# SCH_MATIASALFARO_PROYECTOFINAL.net
KiCad netlist of a schematic drawn in Altium Designer
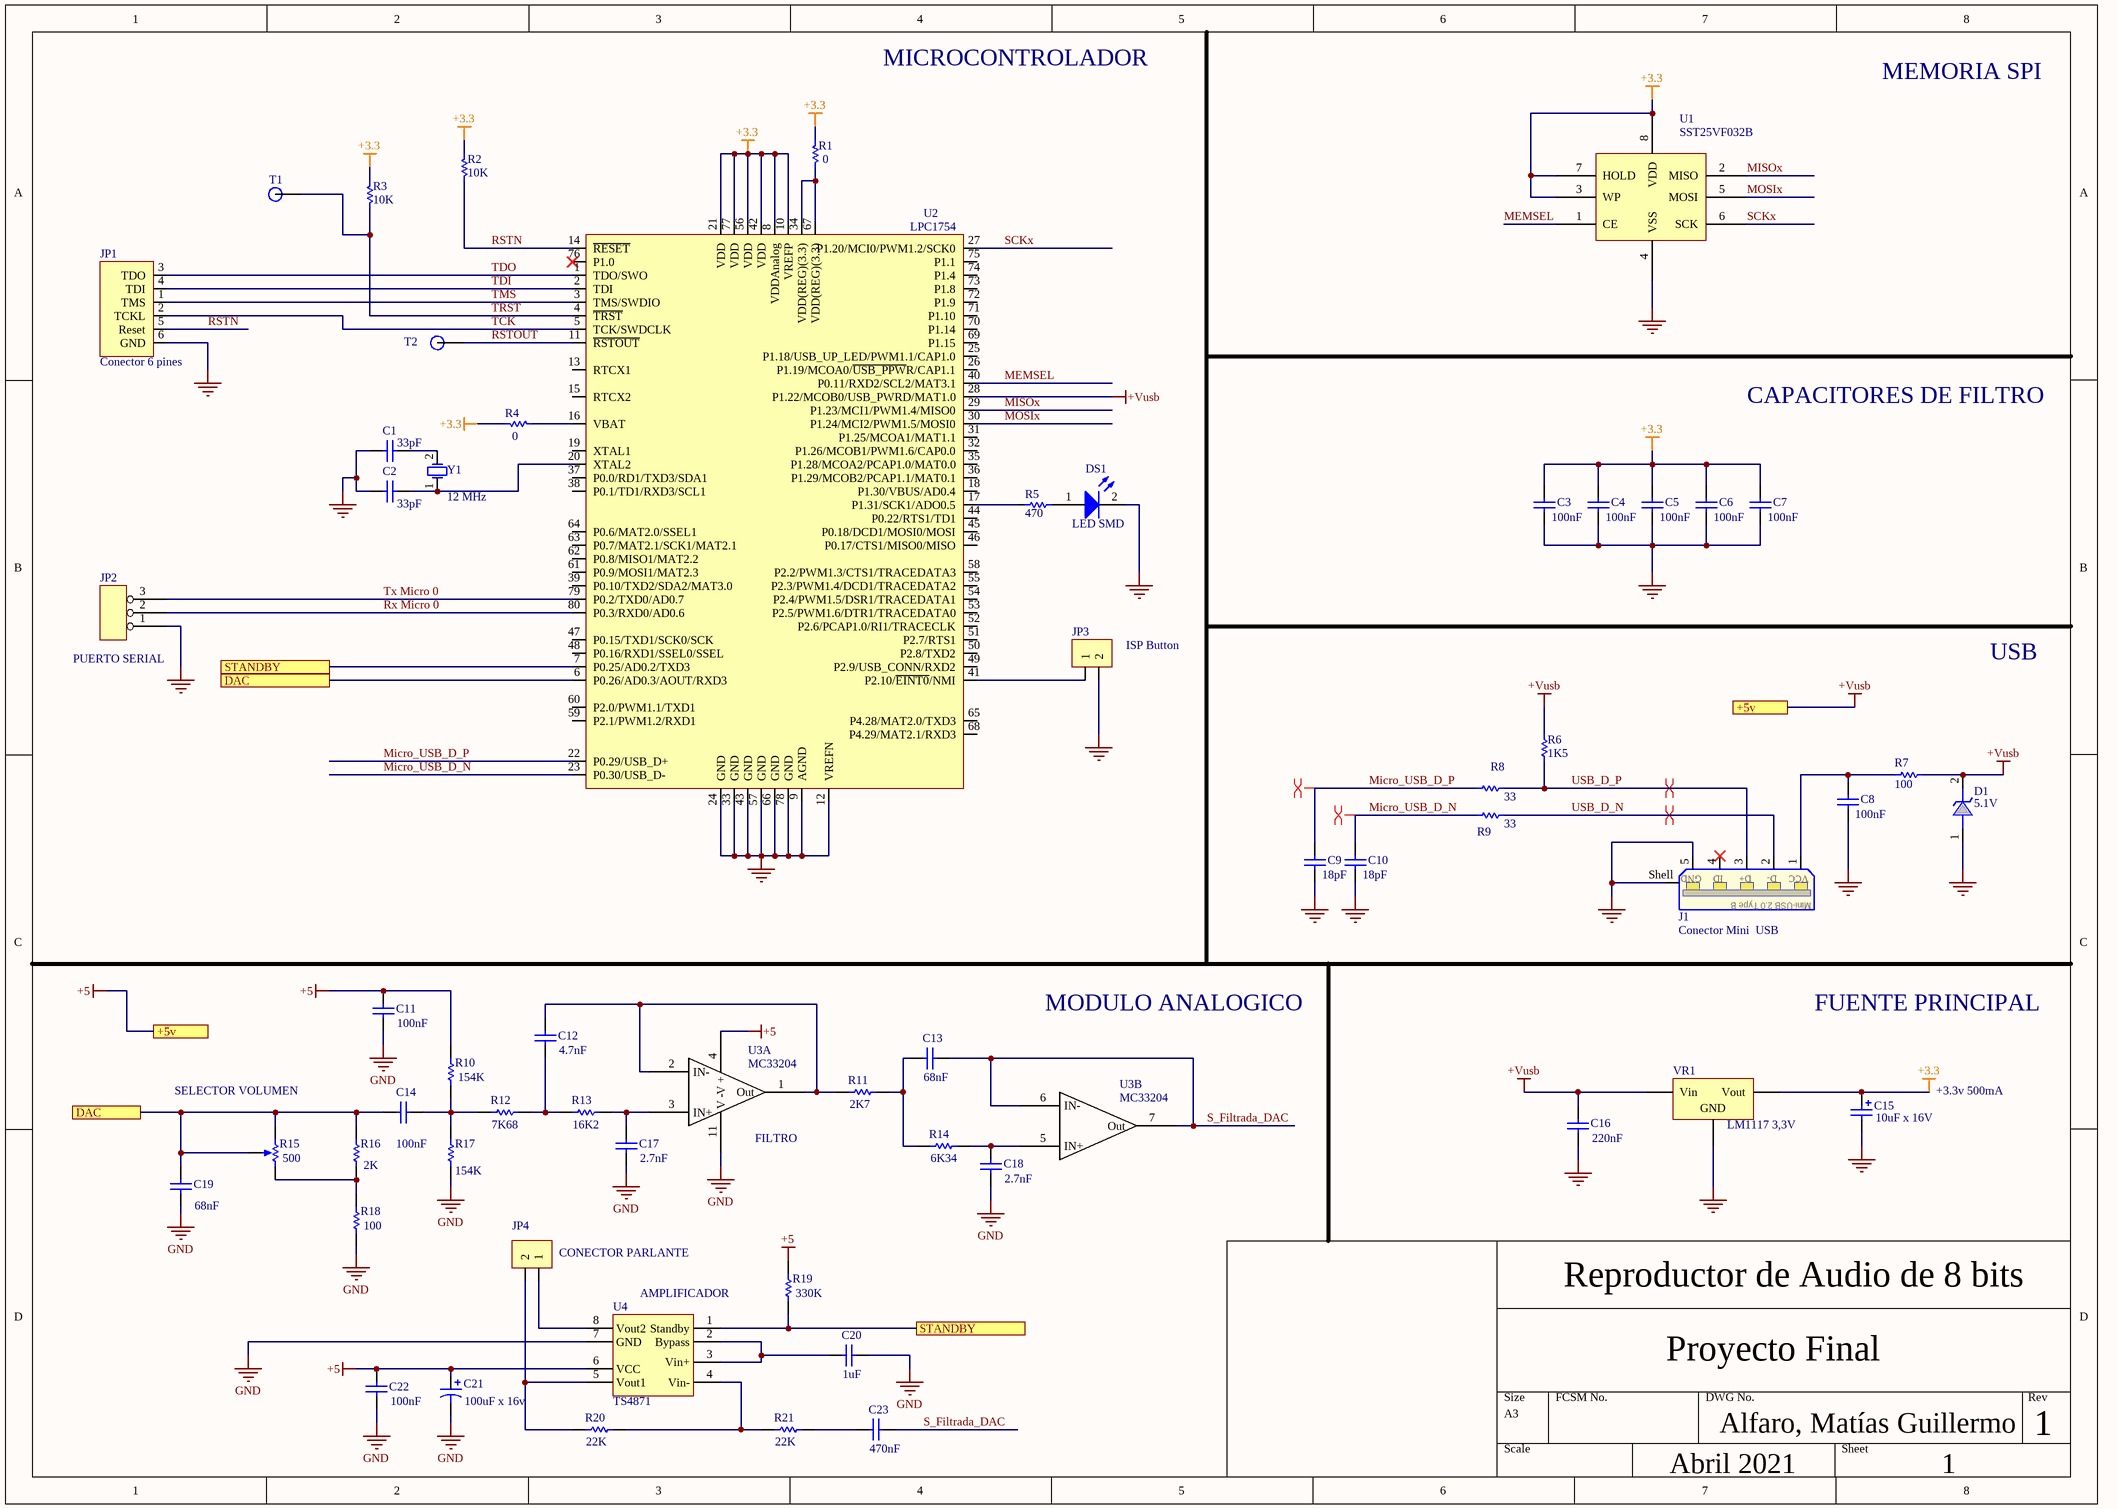
[diagram p0: SCH_MATIASALFARO_PROYECTOFINAL.SchDoc]

(export (version "E")
  (design (tool "Eeschema 10.0.6"))
  (components
    (comp (ref "C1")
      (value "33pF")
      (footprint "C 0805")
      (description "Capacitor")
      (fields (field (name "Comment") "Cap 33pF") (field (name "PUBLISHER") "Altium Limited"))
      (libsource (lib "Miscellaneous Devices") (part "Cap"))
    )
    (comp (ref "C2")
      (value "33pF")
      (footprint "C 0805")
      (description "Capacitor")
      (fields (field (name "Comment") "Cap 33pF") (field (name "PUBLISHER") "Altium Limited"))
      (libsource (lib "Miscellaneous Devices") (part "Cap"))
    )
    (comp (ref "C3")
      (value "100nF")
      (footprint "C 0805")
      (description "Capacitor")
      (fields (field (name "Comment") "Cap 100nF") (field (name "PUBLISHER") "Altium Limited"))
      (libsource (lib "Miscellaneous Devices") (part "Cap"))
    )
    (comp (ref "C4")
      (value "100nF")
      (footprint "C 0805")
      (description "Capacitor")
      (fields (field (name "Comment") "Cap 100nF") (field (name "PUBLISHER") "Altium Limited"))
      (libsource (lib "Miscellaneous Devices") (part "Cap"))
    )
    (comp (ref "C5")
      (value "100nF")
      (footprint "C 0805")
      (description "Capacitor")
      (fields (field (name "Comment") "Cap 100nF") (field (name "PUBLISHER") "Altium Limited"))
      (libsource (lib "Miscellaneous Devices") (part "Cap"))
    )
    (comp (ref "C6")
      (value "100nF")
      (footprint "C 0805")
      (description "Capacitor")
      (fields (field (name "Comment") "Cap 100nF") (field (name "PUBLISHER") "Altium Limited"))
      (libsource (lib "Miscellaneous Devices") (part "Cap"))
    )
    (comp (ref "C7")
      (value "100nF")
      (footprint "C 0805")
      (description "Capacitor")
      (fields (field (name "Comment") "Cap 100nF") (field (name "PUBLISHER") "Altium Limited"))
      (libsource (lib "Miscellaneous Devices") (part "Cap"))
    )
    (comp (ref "C8")
      (value "100nF")
      (footprint "C 0805")
      (description "Capacitor")
      (fields (field (name "Comment") "Cap 100nF") (field (name "PUBLISHER") "Altium Limited"))
      (libsource (lib "Miscellaneous Devices") (part "Cap"))
    )
    (comp (ref "C9")
      (value "18pF")
      (footprint "C 0805")
      (description "Capacitor")
      (fields (field (name "Comment") "Cap 18pF") (field (name "PUBLISHER") "Altium Limited"))
      (libsource (lib "Miscellaneous Devices") (part "Cap"))
    )
    (comp (ref "C10")
      (value "18pF")
      (footprint "C 0805")
      (description "Capacitor")
      (fields (field (name "Comment") "Cap 18pF") (field (name "PUBLISHER") "Altium Limited"))
      (libsource (lib "Miscellaneous Devices") (part "Cap"))
    )
    (comp (ref "C11")
      (value "100nF")
      (footprint "C 0805")
      (description "Capacitor")
      (fields (field (name "Comment") "Cap 100nF") (field (name "PUBLISHER") "Altium Limited"))
      (libsource (lib "Miscellaneous Devices") (part "Cap"))
    )
    (comp (ref "C12")
      (value "4.7nF")
      (footprint "C 0805")
      (description "Capacitor")
      (fields (field (name "Comment") "Cap 4.7nF") (field (name "PUBLISHER") "Altium Limited"))
      (libsource (lib "Miscellaneous Devices") (part "Cap"))
    )
    (comp (ref "C13")
      (value "68nF")
      (footprint "C 0805")
      (description "Capacitor")
      (fields (field (name "Comment") "Cap 68nF") (field (name "PUBLISHER") "Altium Limited"))
      (libsource (lib "Miscellaneous Devices") (part "Cap"))
    )
    (comp (ref "C14")
      (value "100nF")
      (footprint "C 0805")
      (description "Capacitor")
      (fields (field (name "Comment") "Cap 100nF") (field (name "PUBLISHER") "Altium Limited"))
      (libsource (lib "Miscellaneous Devices") (part "Cap"))
    )
    (comp (ref "C15")
      (value "10uF x 16V")
      (footprint "c 0805 Tantalio")
      (description "Capacitor Electrolitico")
      (fields
        (field (name "MANUFACTURER") "Generic Components")
        (field (name "Comment") "Cap 10uF x 16V")
        (field (name "PUBLISHER") "Altium Limited")
      )
      (libsource (lib "DG 128 en Tango SMD") (part "Cap Pol1"))
    )
    (comp (ref "C16")
      (value "220nF")
      (footprint "C 0805")
      (description "Capacitor")
      (fields (field (name "Comment") "Cap 220nF") (field (name "PUBLISHER") "Altium Limited"))
      (libsource (lib "Miscellaneous Devices") (part "Cap"))
    )
    (comp (ref "C17")
      (value "2.7nF")
      (footprint "C 0805")
      (description "Capacitor")
      (fields (field (name "Comment") "Cap 2.7nF") (field (name "PUBLISHER") "Altium Limited"))
      (libsource (lib "Miscellaneous Devices") (part "Cap"))
    )
    (comp (ref "C18")
      (value "2.7nF")
      (footprint "C 0805")
      (description "Capacitor")
      (fields (field (name "Comment") "Cap 2.7nF") (field (name "PUBLISHER") "Altium Limited"))
      (libsource (lib "Miscellaneous Devices") (part "Cap"))
    )
    (comp (ref "C19")
      (value "68nF")
      (footprint "C 0805")
      (description "Capacitor")
      (fields (field (name "Comment") "Cap 68nF") (field (name "PUBLISHER") "Altium Limited"))
      (libsource (lib "Miscellaneous Devices") (part "Cap"))
    )
    (comp (ref "C20")
      (value "1uF")
      (footprint "C 0805")
      (description "Capacitor")
      (fields (field (name "Comment") "Cap 1uF") (field (name "PUBLISHER") "Altium Limited"))
      (libsource (lib "Miscellaneous Devices") (part "Cap"))
    )
    (comp (ref "C21")
      (value "100uF x 16v")
      (footprint "c 0805 Tantalio")
      (description "Polarized Capacitor (Radial)")
      (fields (field (name "Comment") "Cap 100uF x 16v") (field (name "PUBLISHER") "Altium Limited"))
      (libsource (lib "Miscellaneous Devices") (part "Cap Pol1"))
    )
    (comp (ref "C22")
      (value "100nF")
      (footprint "C 0805")
      (description "Capacitor")
      (fields (field (name "Comment") "Cap 100nF") (field (name "PUBLISHER") "Altium Limited"))
      (libsource (lib "Miscellaneous Devices") (part "Cap"))
    )
    (comp (ref "C23")
      (value "470nF")
      (footprint "C 0805")
      (description "Capacitor")
      (fields (field (name "Comment") "Cap 470nF") (field (name "PUBLISHER") "Altium Limited"))
      (libsource (lib "Miscellaneous Devices") (part "Cap"))
    )
    (comp (ref "D1")
      (value "5.1V")
      (footprint "DIODE_SMC")
      (description "Diodo Zener")
      (libsource (lib "*") (part "DIODE ZENER1"))
    )
    (comp (ref "DS1")
      (value "LED SMD")
      (footprint "LED 1206 RED")
      (description "Led Color Verde")
      (fields (field (name "MANUFACTURER") "Generic Components") (field (name "PUBLISHER") "Altium Limited"))
      (libsource (lib "Display SMD") (part "LED1"))
    )
    (comp (ref "J1")
      (value "Conector Mini  USB")
      (footprint "Mini USB Hembra 90º DIP")
      (description "WR-COM Mini USB 2.0 Type B Vertical 5 Contacts")
      (fields (field (name "PARTNUMBER") "651005136421") (field (name "PUBLISHER") "Wurth Elektronik"))
      (libsource (lib "ALTIUM-WR-COM-rev1") (part "651005136421"))
    )
    (comp (ref "JP1")
      (value "Conector 6 pines")
      (footprint "Bornera 6 (2.54mm)")
      (description "Conector Hembra 90º")
      (fields (field (name "MANUFACTURER") "Generic Components"))
      (libsource (lib "DG 128 en Tango SMD") (part "Header 6"))
    )
    (comp (ref "JP2")
      (value "PUERTO SERIAL")
      (footprint "Bornera 3 (5mm)")
      (description "PINES")
      (libsource (lib "Libreris_SCH_2011") (part "HEADER 3"))
    )
    (comp (ref "JP3")
      (value "Pines M. a 90º + Jumper")
      (footprint "Bornera 2 (2.54mm)")
      (description "Pines Macho")
      (libsource (lib "DG 128 en Tango SMD") (part "ConectorX2"))
    )
    (comp (ref "JP4")
      (value "Pines M. a 90º + Jumper")
      (footprint "Bornera 2 (2.54mm)")
      (description "Pines Macho")
      (libsource (lib "") (part "ConectorX2_1"))
    )
    (comp (ref "R1")
      (value "0")
      (footprint "R 0805")
      (description "Resistencia")
      (fields
        (field (name "MANUFACTURER") "Generic Components")
        (field (name "Comment") "Res 0")
        (field (name "PUBLISHER") "Altium Limited")
      )
      (libsource (lib "") (part "Res1_1"))
    )
    (comp (ref "R2")
      (value "10K")
      (footprint "R 0805")
      (description "Resistencia")
      (fields
        (field (name "MANUFACTURER") "Generic Components")
        (field (name "Comment") "Res 10K")
        (field (name "PUBLISHER") "Altium Limited")
      )
      (libsource (lib "") (part "Res1_1"))
    )
    (comp (ref "R3")
      (value "10K")
      (footprint "R 0805")
      (description "Resistencia")
      (fields
        (field (name "MANUFACTURER") "Generic Components")
        (field (name "Comment") "Res 10K")
        (field (name "PUBLISHER") "Altium Limited")
      )
      (libsource (lib "") (part "Res1_1"))
    )
    (comp (ref "R4")
      (value "0")
      (footprint "R 0805")
      (description "Resistencia")
      (fields
        (field (name "MANUFACTURER") "Generic Components")
        (field (name "Comment") "Res 0")
        (field (name "PUBLISHER") "Altium Limited")
      )
      (libsource (lib "") (part "Res1_2"))
    )
    (comp (ref "R5")
      (value "470")
      (footprint "R 0805")
      (description "Resistencia")
      (fields
        (field (name "MANUFACTURER") "Generic Components")
        (field (name "Comment") "Res 470")
        (field (name "PUBLISHER") "Altium Limited")
      )
      (libsource (lib "Universal SCH") (part "Res1"))
    )
    (comp (ref "R6")
      (value "1K5")
      (footprint "R 0805")
      (description "Resistencia")
      (fields
        (field (name "MANUFACTURER") "Generic Components")
        (field (name "Comment") "Res 1K5")
        (field (name "PUBLISHER") "Altium Limited")
      )
      (libsource (lib "") (part "Res1_1"))
    )
    (comp (ref "R7")
      (value "100")
      (footprint "R 0805")
      (description "Resistencia")
      (fields
        (field (name "MANUFACTURER") "Generic Components")
        (field (name "Comment") "Res 100")
        (field (name "PUBLISHER") "Altium Limited")
      )
      (libsource (lib "") (part "Res1_1"))
    )
    (comp (ref "R8")
      (value "33")
      (footprint "R 0805")
      (description "Resistencia")
      (fields
        (field (name "MANUFACTURER") "Generic Components")
        (field (name "Comment") "Res 33")
        (field (name "PUBLISHER") "Altium Limited")
      )
      (libsource (lib "") (part "Res1_1"))
    )
    (comp (ref "R9")
      (value "33")
      (footprint "R 0805")
      (description "Resistencia")
      (fields
        (field (name "MANUFACTURER") "Generic Components")
        (field (name "Comment") "Res 33")
        (field (name "PUBLISHER") "Altium Limited")
      )
      (libsource (lib "") (part "Res1_1"))
    )
    (comp (ref "R10")
      (value "154K")
      (footprint "R 0805")
      (description "Resistor")
      (fields (field (name "Comment") "Res 154K") (field (name "PUBLISHER") "Altium Limited"))
      (libsource (lib "Miscellaneous Devices") (part "Res1"))
    )
    (comp (ref "R11")
      (value "2K7")
      (footprint "R 0805")
      (description "Resistor")
      (fields (field (name "Comment") "Res 2K7") (field (name "PUBLISHER") "Altium Limited"))
      (libsource (lib "Miscellaneous Devices") (part "Res1"))
    )
    (comp (ref "R12")
      (value "7K68")
      (footprint "R 0805")
      (description "Resistor")
      (fields (field (name "Comment") "Res 7K68") (field (name "PUBLISHER") "Altium Limited"))
      (libsource (lib "Miscellaneous Devices") (part "Res1"))
    )
    (comp (ref "R13")
      (value "16K2")
      (footprint "R 0805")
      (description "Resistor")
      (fields (field (name "Comment") "Res 16K2") (field (name "PUBLISHER") "Altium Limited"))
      (libsource (lib "Miscellaneous Devices") (part "Res1"))
    )
    (comp (ref "R14")
      (value "6K34")
      (footprint "R 0805")
      (description "Resistor")
      (fields (field (name "Comment") "Res 6K34") (field (name "PUBLISHER") "Altium Limited"))
      (libsource (lib "Miscellaneous Devices") (part "Res1"))
    )
    (comp (ref "R15")
      (value "500")
      (footprint "VR5")
      (description "Potentiometer")
      (fields (field (name "Comment") "RPot 500") (field (name "PUBLISHER") "Altium Limited"))
      (libsource (lib "Miscellaneous Devices") (part "RPot"))
    )
    (comp (ref "R16")
      (value "2K")
      (footprint "R 0805")
      (description "Resistor")
      (fields (field (name "Comment") "Res 2K") (field (name "PUBLISHER") "Altium Limited"))
      (libsource (lib "Miscellaneous Devices") (part "Res1"))
    )
    (comp (ref "R17")
      (value "154K")
      (footprint "R 0805")
      (description "Resistor")
      (fields (field (name "Comment") "Res 154K") (field (name "PUBLISHER") "Altium Limited"))
      (libsource (lib "Miscellaneous Devices") (part "Res1"))
    )
    (comp (ref "R18")
      (value "100")
      (footprint "R 0805")
      (description "Resistor")
      (fields (field (name "Comment") "Res 100") (field (name "PUBLISHER") "Altium Limited"))
      (libsource (lib "Miscellaneous Devices") (part "Res1"))
    )
    (comp (ref "R19")
      (value "330K")
      (footprint "R 0805")
      (description "Resistor")
      (fields (field (name "Comment") "Res 330K") (field (name "PUBLISHER") "Altium Limited"))
      (libsource (lib "Miscellaneous Devices") (part "Res1"))
    )
    (comp (ref "R20")
      (value "22K")
      (footprint "R 0805")
      (description "Resistor")
      (fields (field (name "Comment") "Res 22K") (field (name "PUBLISHER") "Altium Limited"))
      (libsource (lib "Miscellaneous Devices") (part "Res1"))
    )
    (comp (ref "R21")
      (value "22K")
      (footprint "R 0805")
      (description "Resistor")
      (fields (field (name "Comment") "Res 22K") (field (name "PUBLISHER") "Altium Limited"))
      (libsource (lib "Miscellaneous Devices") (part "Res1"))
    )
    (comp (ref "T1")
      (value "Test Point")
      (footprint "TestPoint Keystone 5000 Silver-Red")
      (libsource (lib "Universal SCH") (part "UNIPIN"))
    )
    (comp (ref "T2")
      (value "Test Point")
      (footprint "TestPoint Keystone 5000 Silver-Red")
      (libsource (lib "Universal SCH") (part "UNIPIN"))
    )
    (comp (ref "U1")
      (value "SST25VF032B")
      (footprint "SO8_L")
      (libsource (lib "Universal SCH") (part "SST25VF032B"))
    )
    (comp (ref "U2")
      (value "LPC1754")
      (description "Microcontrolador LPC1754")
      (libsource (lib "Universal SCH") (part "LPC1754"))
    )
    (comp (ref "U3")
      (value "MC33204")
      (footprint "D014_M")
      (description "4 x Amplificador Operacional")
      (libsource (lib "matias_sch_libreria") (part "MC33204"))
    )
    (comp (ref "U4")
      (value "TS4871")
      (footprint "SO8_M")
      (libsource (lib "matias_sch_libreria") (part "TS4871"))
    )
    (comp (ref "VR1")
      (value "LM1117 3,3V")
      (footprint "SOT223_L")
      (description "Voltage Regulator")
      (fields (field (name "PUBLISHER") "Altium Limited"))
      (libsource (lib "Miscellaneous Devices") (part "Volt Reg"))
    )
    (comp (ref "Y1")
      (value "12 MHz")
      (footprint "Cristal")
      (description "Cristal")
      (fields (field (name "MANUFACTURER") "Generic Components") (field (name "PUBLISHER") "Altium Limited"))
      (libsource (lib "DG 128 en Tango SMD") (part "XTAL"))
    )
  )
  (nets
    (net (code "1") (name "+3.3") (class "Default")
      (node (ref "C15") (pin "1") (pinfunction "1_1") (pintype "passive"))
      (node (ref "C3") (pin "2") (pinfunction "2_2") (pintype "passive"))
      (node (ref "C4") (pin "2") (pinfunction "2_2") (pintype "passive"))
      (node (ref "C5") (pin "2") (pinfunction "2_2") (pintype "passive"))
      (node (ref "C6") (pin "2") (pinfunction "2_2") (pintype "passive"))
      (node (ref "C7") (pin "2") (pinfunction "2_2") (pintype "passive"))
      (node (ref "R1") (pin "2") (pinfunction "2_2") (pintype "passive"))
      (node (ref "R2") (pin "2") (pinfunction "2_2") (pintype "passive"))
      (node (ref "R3") (pin "2") (pinfunction "2_2") (pintype "passive"))
      (node (ref "R4") (pin "2") (pinfunction "2_2") (pintype "passive"))
      (node (ref "U1") (pin "3") (pinfunction "WP_3") (pintype "passive"))
      (node (ref "U1") (pin "7") (pinfunction "HOLD_7") (pintype "passive"))
      (node (ref "U1") (pin "8") (pinfunction "VDD_8") (pintype "passive"))
      (node (ref "U2") (pin "10") (pinfunction "VREFP_10") (pintype "passive"))
      (node (ref "U2") (pin "21") (pinfunction "VDD_21") (pintype "passive"))
      (node (ref "U2") (pin "42") (pinfunction "VDD_42") (pintype "passive"))
      (node (ref "U2") (pin "56") (pinfunction "VDD_56") (pintype "passive"))
      (node (ref "U2") (pin "77") (pinfunction "VDD_77") (pintype "passive"))
      (node (ref "U2") (pin "8") (pinfunction "VDDAnalog_8") (pintype "passive"))
      (node (ref "VR1") (pin "3") (pinfunction "Vout_3") (pintype "passive"))
    )
    (net (code "2") (name "+5") (class "Default")
      (node (ref "C11") (pin "1") (pinfunction "1_1") (pintype "passive"))
      (node (ref "C16") (pin "1") (pinfunction "1_1") (pintype "passive"))
      (node (ref "C21") (pin "1") (pinfunction "1_1") (pintype "passive"))
      (node (ref "C22") (pin "2") (pinfunction "2_2") (pintype "passive"))
      (node (ref "D1") (pin "2") (pinfunction "CATHODE_2") (pintype "passive"))
      (node (ref "R10") (pin "2") (pinfunction "2_2") (pintype "passive"))
      (node (ref "R19") (pin "1") (pinfunction "1_1") (pintype "passive"))
      (node (ref "R6") (pin "2") (pinfunction "2_2") (pintype "passive"))
      (node (ref "R7") (pin "1") (pinfunction "1_1") (pintype "passive"))
      (node (ref "U2") (pin "28") (pinfunction "P1.22/MCOB0/USB_PWRD/MAT1.0_28") (pintype "passive"))
      (node (ref "U3") (pin "4") (pinfunction "V_+_4") (pintype "passive"))
      (node (ref "U4") (pin "6") (pinfunction "VCC_6") (pintype "passive"))
      (node (ref "VR1") (pin "1") (pinfunction "Vin_1") (pintype "passive"))
    )
    (net (code "3") (name "/DAC") (class "Default")
      (node (ref "C14") (pin "1") (pinfunction "1_1") (pintype "passive"))
      (node (ref "C19") (pin "2") (pinfunction "2_2") (pintype "passive"))
      (node (ref "R15") (pin "1") (pinfunction "TOP_1") (pintype "passive"))
      (node (ref "R15") (pin "3") (pinfunction "TAP_3") (pintype "passive"))
      (node (ref "R16") (pin "2") (pinfunction "2_2") (pintype "passive"))
      (node (ref "U2") (pin "6") (pinfunction "P0.26/AD0.3/AOUT/RXD3_6") (pintype "passive"))
    )
    (net (code "4") (name "/MEMSEL") (class "Default")
      (node (ref "U1") (pin "1") (pinfunction "CE_1") (pintype "passive"))
      (node (ref "U2") (pin "40") (pinfunction "P0.11/RXD2/SCL2/MAT3.1_40") (pintype "passive"))
    )
    (net (code "5") (name "/MISOx") (class "Default")
      (node (ref "U1") (pin "2") (pinfunction "MISO_2") (pintype "passive"))
      (node (ref "U2") (pin "29") (pinfunction "P1.23/MCI1/PWM1.4/MISO0_29") (pintype "passive"))
    )
    (net (code "6") (name "/MOSIx") (class "Default")
      (node (ref "U1") (pin "5") (pinfunction "MOSI_5") (pintype "passive"))
      (node (ref "U2") (pin "30") (pinfunction "P1.24/MCI2/PWM1.5/MOSI0_30") (pintype "passive"))
    )
    (net (code "7") (name "/Micro_USB_D_N") (class "Default")
      (node (ref "C10") (pin "2") (pinfunction "2_2") (pintype "passive"))
      (node (ref "R9") (pin "2") (pinfunction "2_2") (pintype "passive"))
      (node (ref "U2") (pin "23") (pinfunction "P0.30/USB_D-_23") (pintype "passive"))
    )
    (net (code "8") (name "/Micro_USB_D_P") (class "Default")
      (node (ref "C9") (pin "2") (pinfunction "2_2") (pintype "passive"))
      (node (ref "R8") (pin "2") (pinfunction "2_2") (pintype "passive"))
      (node (ref "U2") (pin "22") (pinfunction "P0.29/USB_D+_22") (pintype "passive"))
    )
    (net (code "9") (name "/RSTN") (class "Default")
      (node (ref "JP1") (pin "5") (pinfunction "Reset_5") (pintype "passive"))
      (node (ref "R2") (pin "1") (pinfunction "1_1") (pintype "passive"))
      (node (ref "U2") (pin "14") (pinfunction "~{RESET}_14") (pintype "passive"))
    )
    (net (code "10") (name "/RSTOUT") (class "Default")
      (node (ref "T2") (pin "1") (pinfunction "1_1") (pintype "passive"))
      (node (ref "U2") (pin "11") (pinfunction "~{RSTOUT}_11") (pintype "passive"))
    )
    (net (code "11") (name "/Rx Micro 0") (class "Default")
      (node (ref "JP2") (pin "2") (pintype "passive"))
      (node (ref "U2") (pin "80") (pinfunction "P0.3/RXD0/AD0.6_80") (pintype "passive"))
    )
    (net (code "12") (name "/SCKx") (class "Default")
      (node (ref "U1") (pin "6") (pinfunction "SCK_6") (pintype "passive"))
      (node (ref "U2") (pin "27") (pinfunction "P1.20/MCI0/PWM1.2/SCK0_27") (pintype "passive"))
    )
    (net (code "13") (name "/STANDBY") (class "Default")
      (node (ref "R19") (pin "2") (pinfunction "2_2") (pintype "passive"))
      (node (ref "U2") (pin "7") (pinfunction "P0.25/AD0.2/TXD3_7") (pintype "passive"))
      (node (ref "U4") (pin "1") (pinfunction "Standby_1") (pintype "passive"))
    )
    (net (code "14") (name "/S_Filtrada_DAC") (class "Default")
      (node (ref "C13") (pin "2") (pinfunction "2_2") (pintype "passive"))
      (node (ref "C23") (pin "2") (pinfunction "2_2") (pintype "passive"))
      (node (ref "U3") (pin "6") (pinfunction "IN-_6") (pintype "passive"))
      (node (ref "U3") (pin "7") (pinfunction "Out_7") (pintype "passive"))
    )
    (net (code "15") (name "/TCK") (class "Default")
      (node (ref "JP1") (pin "2") (pinfunction "TCKL_2") (pintype "passive"))
      (node (ref "U2") (pin "5") (pinfunction "TCK/SWDCLK_5") (pintype "passive"))
    )
    (net (code "16") (name "/TDI") (class "Default")
      (node (ref "JP1") (pin "4") (pinfunction "TDI_4") (pintype "passive"))
      (node (ref "U2") (pin "2") (pinfunction "TDI_2") (pintype "passive"))
    )
    (net (code "17") (name "/TDO") (class "Default")
      (node (ref "JP1") (pin "3") (pinfunction "TDO_3") (pintype "passive"))
      (node (ref "U2") (pin "1") (pinfunction "TDO/SWO_1") (pintype "passive"))
    )
    (net (code "18") (name "/TMS") (class "Default")
      (node (ref "JP1") (pin "1") (pinfunction "TMS_1") (pintype "passive"))
      (node (ref "U2") (pin "3") (pinfunction "TMS/SWDIO_3") (pintype "passive"))
    )
    (net (code "19") (name "/TRST") (class "Default")
      (node (ref "R3") (pin "1") (pinfunction "1_1") (pintype "passive"))
      (node (ref "T1") (pin "1") (pinfunction "1_1") (pintype "passive"))
      (node (ref "U2") (pin "4") (pinfunction "~{TRST}_4") (pintype "passive"))
    )
    (net (code "20") (name "/Tx Micro 0") (class "Default")
      (node (ref "JP2") (pin "3") (pintype "passive"))
      (node (ref "U2") (pin "79") (pinfunction "P0.2/TXD0/AD0.7_79") (pintype "passive"))
    )
    (net (code "21") (name "/USB_D_N") (class "Default")
      (node (ref "J1") (pin "2") (pinfunction "D-_2") (pintype "passive"))
      (node (ref "R9") (pin "1") (pinfunction "1_1") (pintype "passive"))
    )
    (net (code "22") (name "/USB_D_P") (class "Default")
      (node (ref "J1") (pin "3") (pinfunction "D+_3") (pintype "passive"))
      (node (ref "R6") (pin "1") (pinfunction "1_1") (pintype "passive"))
      (node (ref "R8") (pin "1") (pinfunction "1_1") (pintype "passive"))
    )
    (net (code "23") (name "GND") (class "Default")
      (node (ref "C1") (pin "1") (pinfunction "1_1") (pintype "passive"))
      (node (ref "C10") (pin "1") (pinfunction "1_1") (pintype "passive"))
      (node (ref "C11") (pin "2") (pinfunction "2_2") (pintype "passive"))
      (node (ref "C15") (pin "2") (pinfunction "2_2") (pintype "passive"))
      (node (ref "C16") (pin "2") (pinfunction "2_2") (pintype "passive"))
      (node (ref "C17") (pin "2") (pinfunction "2_2") (pintype "passive"))
      (node (ref "C18") (pin "1") (pinfunction "1_1") (pintype "passive"))
      (node (ref "C19") (pin "1") (pinfunction "1_1") (pintype "passive"))
      (node (ref "C2") (pin "1") (pinfunction "1_1") (pintype "passive"))
      (node (ref "C20") (pin "2") (pinfunction "2_2") (pintype "passive"))
      (node (ref "C21") (pin "2") (pinfunction "2_2") (pintype "passive"))
      (node (ref "C22") (pin "1") (pinfunction "1_1") (pintype "passive"))
      (node (ref "C3") (pin "1") (pinfunction "1_1") (pintype "passive"))
      (node (ref "C4") (pin "1") (pinfunction "1_1") (pintype "passive"))
      (node (ref "C5") (pin "1") (pinfunction "1_1") (pintype "passive"))
      (node (ref "C6") (pin "1") (pinfunction "1_1") (pintype "passive"))
      (node (ref "C7") (pin "1") (pinfunction "1_1") (pintype "passive"))
      (node (ref "C8") (pin "1") (pinfunction "1_1") (pintype "passive"))
      (node (ref "C9") (pin "1") (pinfunction "1_1") (pintype "passive"))
      (node (ref "D1") (pin "1") (pinfunction "ANODE_1") (pintype "passive"))
      (node (ref "DS1") (pin "2") (pinfunction "K_2") (pintype "passive"))
      (node (ref "J1") (pin "5") (pinfunction "GND_5") (pintype "passive"))
      (node (ref "J1") (pin "Shell") (pinfunction "Shell_Shell") (pintype "passive"))
      (node (ref "JP1") (pin "6") (pinfunction "GND_6") (pintype "passive"))
      (node (ref "JP2") (pin "1") (pintype "passive"))
      (node (ref "JP3") (pin "2") (pinfunction "2_2") (pintype "passive"))
      (node (ref "R17") (pin "1") (pinfunction "1_1") (pintype "passive"))
      (node (ref "R18") (pin "1") (pinfunction "1_1") (pintype "passive"))
      (node (ref "U1") (pin "4") (pinfunction "VSS_4") (pintype "passive"))
      (node (ref "U2") (pin "12") (pinfunction "VREFN_12") (pintype "passive"))
      (node (ref "U2") (pin "24") (pinfunction "GND_24") (pintype "passive"))
      (node (ref "U2") (pin "33") (pinfunction "GND_33") (pintype "passive"))
      (node (ref "U2") (pin "43") (pinfunction "GND_43") (pintype "passive"))
      (node (ref "U2") (pin "57") (pinfunction "GND_57") (pintype "passive"))
      (node (ref "U2") (pin "66") (pinfunction "GND_66") (pintype "passive"))
      (node (ref "U2") (pin "78") (pinfunction "GND_78") (pintype "passive"))
      (node (ref "U2") (pin "9") (pinfunction "AGND_9") (pintype "passive"))
      (node (ref "U3") (pin "11") (pinfunction "V_-_11") (pintype "passive"))
      (node (ref "U4") (pin "7") (pinfunction "GND_7") (pintype "passive"))
      (node (ref "VR1") (pin "2") (pinfunction "GND_2") (pintype "passive"))
    )
    (net (code "24") (name "Net-(C12-Pad2)") (class "Default")
      (node (ref "C12") (pin "2") (pinfunction "2_2") (pintype "passive"))
      (node (ref "R12") (pin "1") (pinfunction "1_1") (pintype "passive"))
      (node (ref "R13") (pin "2") (pinfunction "2_2") (pintype "passive"))
    )
    (net (code "25") (name "Net-(C13-Pad1)") (class "Default")
      (node (ref "C13") (pin "1") (pinfunction "1_1") (pintype "passive"))
      (node (ref "R11") (pin "1") (pinfunction "1_1") (pintype "passive"))
      (node (ref "R14") (pin "2") (pinfunction "2_2") (pintype "passive"))
    )
    (net (code "26") (name "Net-(C14-Pad2)") (class "Default")
      (node (ref "C14") (pin "2") (pinfunction "2_2") (pintype "passive"))
      (node (ref "R10") (pin "1") (pinfunction "1_1") (pintype "passive"))
      (node (ref "R12") (pin "2") (pinfunction "2_2") (pintype "passive"))
      (node (ref "R17") (pin "2") (pinfunction "2_2") (pintype "passive"))
    )
    (net (code "27") (name "Net-(C23-Pad1)") (class "Default")
      (node (ref "C23") (pin "1") (pinfunction "1_1") (pintype "passive"))
      (node (ref "R21") (pin "1") (pinfunction "1_1") (pintype "passive"))
    )
    (net (code "28") (name "Net-(DS1-A)") (class "Default")
      (node (ref "DS1") (pin "1") (pinfunction "A_1") (pintype "passive"))
      (node (ref "R5") (pin "1") (pinfunction "1_1") (pintype "passive"))
    )
    (net (code "29") (name "Net-(J1-VCC)") (class "Default")
      (node (ref "C8") (pin "2") (pinfunction "2_2") (pintype "passive"))
      (node (ref "J1") (pin "1") (pinfunction "VCC_1") (pintype "passive"))
      (node (ref "R7") (pin "2") (pinfunction "2_2") (pintype "passive"))
    )
    (net (code "30") (name "Net-(R1-Pad1)") (class "Default")
      (node (ref "R1") (pin "1") (pinfunction "1_1") (pintype "passive"))
      (node (ref "U2") (pin "34") (pinfunction "VDD(REG)(3.3)_34") (pintype "passive"))
      (node (ref "U2") (pin "67") (pinfunction "VDD(REG)(3.3)_67") (pintype "passive"))
    )
    (net (code "31") (name "Net-(R15-BOT)") (class "Default")
      (node (ref "R15") (pin "2") (pinfunction "BOT_2") (pintype "passive"))
      (node (ref "R16") (pin "1") (pinfunction "1_1") (pintype "passive"))
      (node (ref "R18") (pin "2") (pinfunction "2_2") (pintype "passive"))
    )
    (net (code "32") (name "Net-(U2-P1.31{slash}SCK1{slash}ADO0.5)") (class "Default")
      (node (ref "R5") (pin "2") (pinfunction "2_2") (pintype "passive"))
      (node (ref "U2") (pin "17") (pinfunction "P1.31/SCK1/ADO0.5_17") (pintype "passive"))
    )
    (net (code "33") (name "Net-(U2-P2.10{slash}~{EINT0}{slash}NMI)") (class "Default")
      (node (ref "JP3") (pin "1") (pinfunction "1_1") (pintype "passive"))
      (node (ref "U2") (pin "41") (pinfunction "P2.10/~{EINT0}/NMI_41") (pintype "passive"))
    )
    (net (code "34") (name "Net-(U2-VBAT)") (class "Default")
      (node (ref "R4") (pin "1") (pinfunction "1_1") (pintype "passive"))
      (node (ref "U2") (pin "16") (pinfunction "VBAT_16") (pintype "passive"))
    )
    (net (code "35") (name "Net-(U2-XTAL2)") (class "Default")
      (node (ref "C2") (pin "2") (pinfunction "2_2") (pintype "passive"))
      (node (ref "U2") (pin "20") (pinfunction "XTAL2_20") (pintype "passive"))
      (node (ref "Y1") (pin "1") (pinfunction "OSC1_1") (pintype "passive"))
    )
    (net (code "36") (name "Net-(U3A-IN+)") (class "Default")
      (node (ref "C17") (pin "1") (pinfunction "1_1") (pintype "passive"))
      (node (ref "R13") (pin "1") (pinfunction "1_1") (pintype "passive"))
      (node (ref "U3") (pin "3") (pinfunction "IN+_3") (pintype "passive"))
    )
    (net (code "37") (name "Net-(U3A-IN-)") (class "Default")
      (node (ref "C12") (pin "1") (pinfunction "1_1") (pintype "passive"))
      (node (ref "R11") (pin "2") (pinfunction "2_2") (pintype "passive"))
      (node (ref "U3") (pin "1") (pinfunction "Out_1") (pintype "passive"))
      (node (ref "U3") (pin "2") (pinfunction "IN-_2") (pintype "passive"))
    )
    (net (code "38") (name "Net-(U3B-IN+)") (class "Default")
      (node (ref "C18") (pin "2") (pinfunction "2_2") (pintype "passive"))
      (node (ref "R14") (pin "1") (pinfunction "1_1") (pintype "passive"))
      (node (ref "U3") (pin "5") (pinfunction "IN+_5") (pintype "passive"))
    )
    (net (code "39") (name "Net-(U4-Bypass)") (class "Default")
      (node (ref "C20") (pin "1") (pinfunction "1_1") (pintype "passive"))
      (node (ref "U4") (pin "2") (pinfunction "Bypass_2") (pintype "passive"))
      (node (ref "U4") (pin "3") (pinfunction "Vin+_3") (pintype "passive"))
    )
    (net (code "40") (name "Net-(U4-Vin-)") (class "Default")
      (node (ref "R20") (pin "1") (pinfunction "1_1") (pintype "passive"))
      (node (ref "R21") (pin "2") (pinfunction "2_2") (pintype "passive"))
      (node (ref "U4") (pin "4") (pinfunction "Vin-_4") (pintype "passive"))
    )
    (net (code "41") (name "Net-(U4-Vout1)") (class "Default")
      (node (ref "JP4") (pin "2") (pinfunction "2_2") (pintype "passive"))
      (node (ref "R20") (pin "2") (pinfunction "2_2") (pintype "passive"))
      (node (ref "U4") (pin "5") (pinfunction "Vout1_5") (pintype "passive"))
    )
    (net (code "42") (name "Net-(U4-Vout2)") (class "Default")
      (node (ref "JP4") (pin "1") (pinfunction "1_1") (pintype "passive"))
      (node (ref "U4") (pin "8") (pinfunction "Vout2_8") (pintype "passive"))
    )
    (net (code "43") (name "Net-(Y1-OSC2)") (class "Default")
      (node (ref "C1") (pin "2") (pinfunction "2_2") (pintype "passive"))
      (node (ref "Y1") (pin "2") (pinfunction "OSC2_2") (pintype "passive"))
    )
    (net (code "44") (name "unconnected-(J1-ID-Pad4)") (class "Default")
      (node (ref "J1") (pin "4") (pinfunction "ID_4") (pintype "passive+no_connect"))
    )
    (net (code "45") (name "unconnected-(U2-P0.0{slash}RD1{slash}TXD3{slash}SDA1-Pad37)") (class "Default")
      (node (ref "U2") (pin "37") (pinfunction "P0.0/RD1/TXD3/SDA1_37") (pintype "passive"))
    )
    (net (code "46") (name "unconnected-(U2-P0.1{slash}TD1{slash}RXD3{slash}SCL1-Pad38)") (class "Default")
      (node (ref "U2") (pin "38") (pinfunction "P0.1/TD1/RXD3/SCL1_38") (pintype "passive"))
    )
    (net (code "47") (name "unconnected-(U2-P0.6{slash}MAT2.0{slash}SSEL1-Pad64)") (class "Default")
      (node (ref "U2") (pin "64") (pinfunction "P0.6/MAT2.0/SSEL1_64") (pintype "passive"))
    )
    (net (code "48") (name "unconnected-(U2-P0.7{slash}MAT2.1{slash}SCK1{slash}MAT2.1-Pad63)") (class "Default")
      (node (ref "U2") (pin "63") (pinfunction "P0.7/MAT2.1/SCK1/MAT2.1_63") (pintype "passive"))
    )
    (net (code "49") (name "unconnected-(U2-P0.8{slash}MISO1{slash}MAT2.2-Pad62)") (class "Default")
      (node (ref "U2") (pin "62") (pinfunction "P0.8/MISO1/MAT2.2_62") (pintype "passive"))
    )
    (net (code "50") (name "unconnected-(U2-P0.9{slash}MOSI1{slash}MAT2.3-Pad61)") (class "Default")
      (node (ref "U2") (pin "61") (pinfunction "P0.9/MOSI1/MAT2.3_61") (pintype "passive"))
    )
    (net (code "51") (name "unconnected-(U2-P0.10{slash}TXD2{slash}SDA2{slash}MAT3.0-Pad39)") (class "Default")
      (node (ref "U2") (pin "39") (pinfunction "P0.10/TXD2/SDA2/MAT3.0_39") (pintype "passive"))
    )
    (net (code "52") (name "unconnected-(U2-P0.15{slash}TXD1{slash}SCK0{slash}SCK-Pad47)") (class "Default")
      (node (ref "U2") (pin "47") (pinfunction "P0.15/TXD1/SCK0/SCK_47") (pintype "passive"))
    )
    (net (code "53") (name "unconnected-(U2-P0.16{slash}RXD1{slash}SSEL0{slash}SSEL-Pad48)") (class "Default")
      (node (ref "U2") (pin "48") (pinfunction "P0.16/RXD1/SSEL0/SSEL_48") (pintype "passive"))
    )
    (net (code "54") (name "unconnected-(U2-P0.17{slash}CTS1{slash}MISO0{slash}MISO-Pad46)") (class "Default")
      (node (ref "U2") (pin "46") (pinfunction "P0.17/CTS1/MISO0/MISO_46") (pintype "passive"))
    )
    (net (code "55") (name "unconnected-(U2-P0.18{slash}DCD1{slash}MOSI0{slash}MOSI-Pad45)") (class "Default")
      (node (ref "U2") (pin "45") (pinfunction "P0.18/DCD1/MOSI0/MOSI_45") (pintype "passive"))
    )
    (net (code "56") (name "unconnected-(U2-P0.22{slash}RTS1{slash}TD1-Pad44)") (class "Default")
      (node (ref "U2") (pin "44") (pinfunction "P0.22/RTS1/TD1_44") (pintype "passive"))
    )
    (net (code "57") (name "unconnected-(U2-P1.0-Pad76)") (class "Default")
      (node (ref "U2") (pin "76") (pinfunction "P1.0_76") (pintype "passive+no_connect"))
    )
    (net (code "58") (name "unconnected-(U2-P1.1-Pad75)") (class "Default")
      (node (ref "U2") (pin "75") (pinfunction "P1.1_75") (pintype "passive"))
    )
    (net (code "59") (name "unconnected-(U2-P1.4-Pad74)") (class "Default")
      (node (ref "U2") (pin "74") (pinfunction "P1.4_74") (pintype "passive"))
    )
    (net (code "60") (name "unconnected-(U2-P1.8-Pad73)") (class "Default")
      (node (ref "U2") (pin "73") (pinfunction "P1.8_73") (pintype "passive"))
    )
    (net (code "61") (name "unconnected-(U2-P1.9-Pad72)") (class "Default")
      (node (ref "U2") (pin "72") (pinfunction "P1.9_72") (pintype "passive"))
    )
    (net (code "62") (name "unconnected-(U2-P1.10-Pad71)") (class "Default")
      (node (ref "U2") (pin "71") (pinfunction "P1.10_71") (pintype "passive"))
    )
    (net (code "63") (name "unconnected-(U2-P1.14-Pad70)") (class "Default")
      (node (ref "U2") (pin "70") (pinfunction "P1.14_70") (pintype "passive"))
    )
    (net (code "64") (name "unconnected-(U2-P1.15-Pad69)") (class "Default")
      (node (ref "U2") (pin "69") (pinfunction "P1.15_69") (pintype "passive"))
    )
    (net (code "65") (name "unconnected-(U2-P1.18{slash}USB_UP_LED{slash}PWM1.1{slash}CAP1.0-Pad25)") (class "Default")
      (node (ref "U2") (pin "25") (pinfunction "P1.18/USB_UP_LED/PWM1.1/CAP1.0_25") (pintype "passive"))
    )
    (net (code "66") (name "unconnected-(U2-P1.19{slash}MCOA0{slash}~{USB_PPW}R{slash}CAP1.1-Pad26)") (class "Default")
      (node (ref "U2") (pin "26") (pinfunction "P1.19/MCOA0/~{USB_PPW}R/CAP1.1_26") (pintype "passive"))
    )
    (net (code "67") (name "unconnected-(U2-P1.25{slash}MCOA1{slash}MAT1.1-Pad31)") (class "Default")
      (node (ref "U2") (pin "31") (pinfunction "P1.25/MCOA1/MAT1.1_31") (pintype "passive"))
    )
    (net (code "68") (name "unconnected-(U2-P1.26{slash}MCOB1{slash}PWM1.6{slash}CAP0.0-Pad32)") (class "Default")
      (node (ref "U2") (pin "32") (pinfunction "P1.26/MCOB1/PWM1.6/CAP0.0_32") (pintype "passive"))
    )
    (net (code "69") (name "unconnected-(U2-P1.28{slash}MCOA2{slash}PCAP1.0{slash}MAT0.0-Pad35)") (class "Default")
      (node (ref "U2") (pin "35") (pinfunction "P1.28/MCOA2/PCAP1.0/MAT0.0_35") (pintype "passive"))
    )
    (net (code "70") (name "unconnected-(U2-P1.29{slash}MCOB2{slash}PCAP1.1{slash}MAT0.1-Pad36)") (class "Default")
      (node (ref "U2") (pin "36") (pinfunction "P1.29/MCOB2/PCAP1.1/MAT0.1_36") (pintype "passive"))
    )
    (net (code "71") (name "unconnected-(U2-P1.30{slash}VBUS{slash}AD0.4-Pad18)") (class "Default")
      (node (ref "U2") (pin "18") (pinfunction "P1.30/VBUS/AD0.4_18") (pintype "passive"))
    )
    (net (code "72") (name "unconnected-(U2-P2.0{slash}PWM1.1{slash}TXD1-Pad60)") (class "Default")
      (node (ref "U2") (pin "60") (pinfunction "P2.0/PWM1.1/TXD1_60") (pintype "passive"))
    )
    (net (code "73") (name "unconnected-(U2-P2.1{slash}PWM1.2{slash}RXD1-Pad59)") (class "Default")
      (node (ref "U2") (pin "59") (pinfunction "P2.1/PWM1.2/RXD1_59") (pintype "passive"))
    )
    (net (code "74") (name "unconnected-(U2-P2.2{slash}PWM1.3{slash}CTS1{slash}TRACEDATA3-Pad58)") (class "Default")
      (node (ref "U2") (pin "58") (pinfunction "P2.2/PWM1.3/CTS1/TRACEDATA3_58") (pintype "passive"))
    )
    (net (code "75") (name "unconnected-(U2-P2.3{slash}PWM1.4{slash}DCD1{slash}TRACEDATA2-Pad55)") (class "Default")
      (node (ref "U2") (pin "55") (pinfunction "P2.3/PWM1.4/DCD1/TRACEDATA2_55") (pintype "passive"))
    )
    (net (code "76") (name "unconnected-(U2-P2.4{slash}PWM1.5{slash}DSR1{slash}TRACEDATA1-Pad54)") (class "Default")
      (node (ref "U2") (pin "54") (pinfunction "P2.4/PWM1.5/DSR1/TRACEDATA1_54") (pintype "passive"))
    )
    (net (code "77") (name "unconnected-(U2-P2.5{slash}PWM1.6{slash}DTR1{slash}TRACEDATA0-Pad53)") (class "Default")
      (node (ref "U2") (pin "53") (pinfunction "P2.5/PWM1.6/DTR1/TRACEDATA0_53") (pintype "passive"))
    )
    (net (code "78") (name "unconnected-(U2-P2.6{slash}PCAP1.0{slash}RI1{slash}TRACECLK-Pad52)") (class "Default")
      (node (ref "U2") (pin "52") (pinfunction "P2.6/PCAP1.0/RI1/TRACECLK_52") (pintype "passive"))
    )
    (net (code "79") (name "unconnected-(U2-P2.7{slash}RTS1-Pad51)") (class "Default")
      (node (ref "U2") (pin "51") (pinfunction "P2.7/RTS1_51") (pintype "passive"))
    )
    (net (code "80") (name "unconnected-(U2-P2.8{slash}TXD2-Pad50)") (class "Default")
      (node (ref "U2") (pin "50") (pinfunction "P2.8/TXD2_50") (pintype "passive"))
    )
    (net (code "81") (name "unconnected-(U2-P2.9{slash}USB_CONN{slash}RXD2-Pad49)") (class "Default")
      (node (ref "U2") (pin "49") (pinfunction "P2.9/USB_CONN/RXD2_49") (pintype "passive"))
    )
    (net (code "82") (name "unconnected-(U2-P4.28{slash}MAT2.0{slash}TXD3-Pad65)") (class "Default")
      (node (ref "U2") (pin "65") (pinfunction "P4.28/MAT2.0/TXD3_65") (pintype "passive"))
    )
    (net (code "83") (name "unconnected-(U2-P4.29{slash}MAT2.1{slash}RXD3-Pad68)") (class "Default")
      (node (ref "U2") (pin "68") (pinfunction "P4.29/MAT2.1/RXD3_68") (pintype "passive"))
    )
    (net (code "84") (name "unconnected-(U2-RTCX1-Pad13)") (class "Default")
      (node (ref "U2") (pin "13") (pinfunction "RTCX1_13") (pintype "passive"))
    )
    (net (code "85") (name "unconnected-(U2-RTCX2-Pad15)") (class "Default")
      (node (ref "U2") (pin "15") (pinfunction "RTCX2_15") (pintype "passive"))
    )
    (net (code "86") (name "unconnected-(U2-XTAL1-Pad19)") (class "Default")
      (node (ref "U2") (pin "19") (pinfunction "XTAL1_19") (pintype "passive"))
    )
  )
)
